# Mechanical.net
KiCad netlist of a schematic drawn in Altium Designer
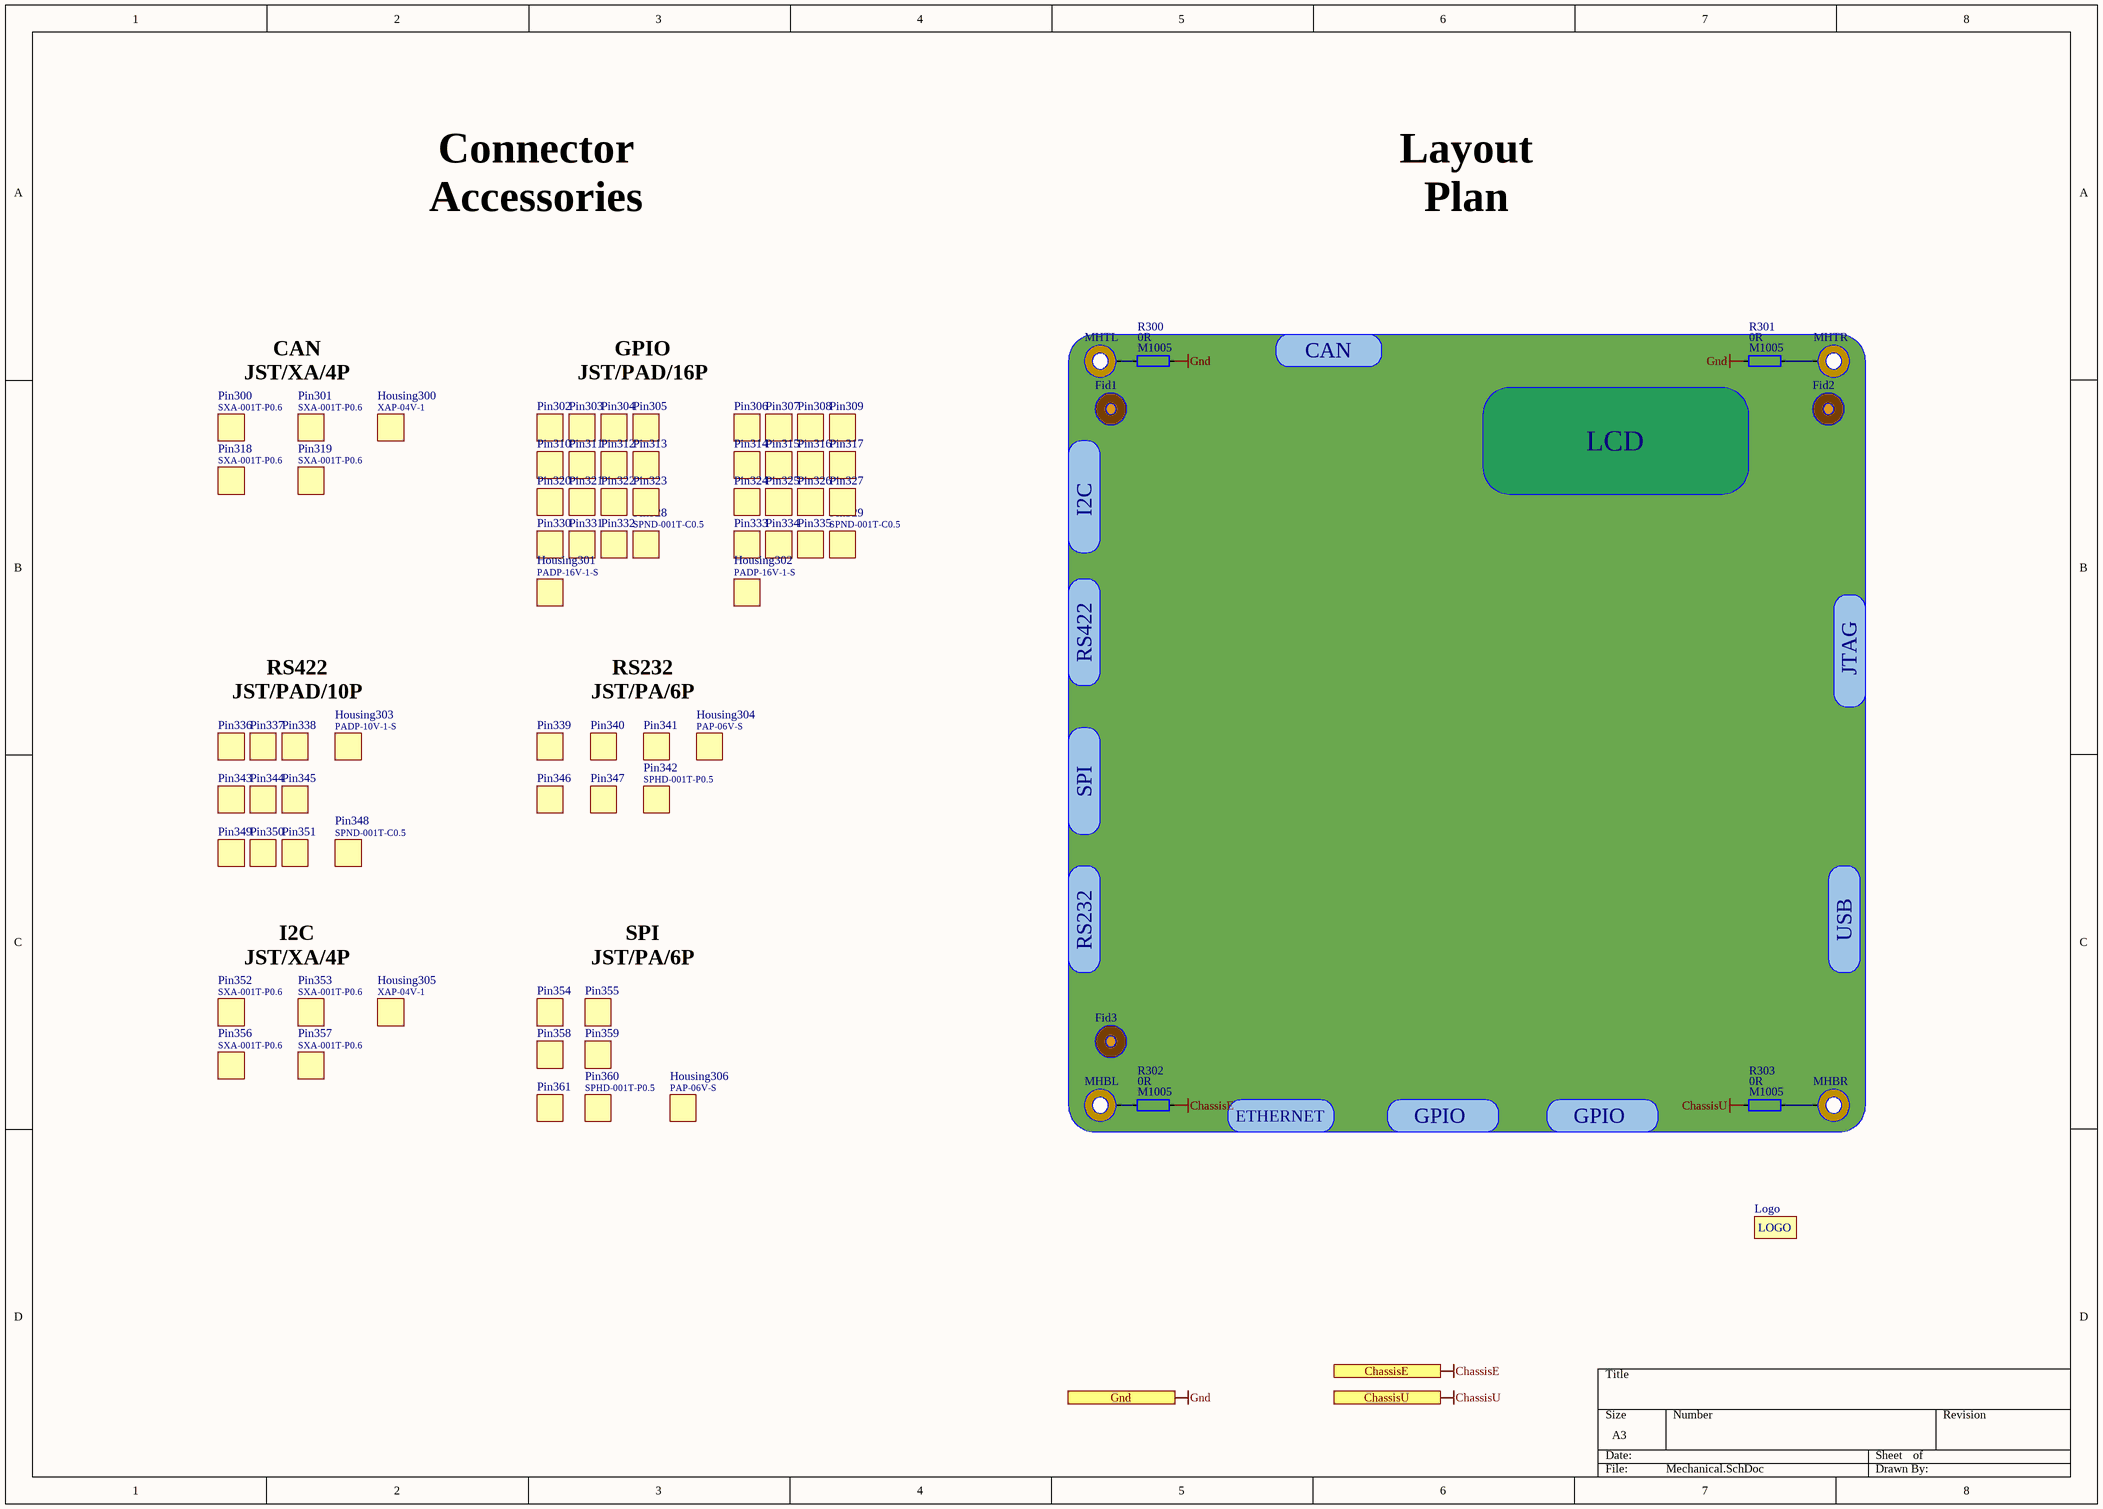
[diagram p0: Mechanical.SchDoc]

(export (version "E")
  (design (tool "Eeschema 10.0.6"))
  (components
    (comp (ref "Fid1")
      (value "Fiducial")
      (footprint "Fiducial - 2mm, 5mm")
      (description "Mechanical, Fiducial, PCB, 2mm/5mm")
      (libsource (lib "Mechanical") (part "Fiducial"))
    )
    (comp (ref "Fid2")
      (value "Fiducial")
      (footprint "Fiducial - 2mm, 5mm")
      (description "Mechanical, Fiducial, PCB, 2mm/5mm")
      (libsource (lib "Mechanical") (part "Fiducial"))
    )
    (comp (ref "Fid3")
      (value "Fiducial")
      (footprint "Fiducial - 2mm, 5mm")
      (description "Mechanical, Fiducial, PCB, 2mm/5mm")
      (libsource (lib "Mechanical") (part "Fiducial"))
    )
    (comp (ref "Housing300")
      (value "Housing")
      (footprint "Housing, PAP-06V-S")
      (description "Housing, JST, 4P, XA")
      (fields (field (name "MANUFACTURER") "JST") (field (name "MANUFACTURER PART NUMBER") "XAP-04V-1"))
      (libsource (lib "Connector - JST") (part "Housing"))
    )
    (comp (ref "Housing301")
      (value "Housing")
      (footprint "Housing, PADP-16V-1-S")
      (description "Housing, JST, 16P, PAD")
      (fields (field (name "MANUFACTURER") "JST") (field (name "MANUFACTURER PART NUMBER") "PADP-16V-1-S"))
      (libsource (lib "Connector - JST") (part "Housing"))
    )
    (comp (ref "Housing302")
      (value "Housing")
      (footprint "Housing, PADP-16V-1-S")
      (description "Housing, JST, 16P, PAD")
      (fields (field (name "MANUFACTURER") "JST") (field (name "MANUFACTURER PART NUMBER") "PADP-16V-1-S"))
      (libsource (lib "Connector - JST") (part "Housing"))
    )
    (comp (ref "Housing303")
      (value "Housing")
      (footprint "Housing, PADP-10V-1-S")
      (description "Housing, JST, 10P, PAD")
      (fields (field (name "MANUFACTURER") "JST") (field (name "MANUFACTURER PART NUMBER") "PADP-10V-1-S"))
      (libsource (lib "Connector - JST") (part "Housing"))
    )
    (comp (ref "Housing304")
      (value "Housing")
      (footprint "Housing, PAP-06V-S")
      (description "Housing, JST, PAP-06V-S")
      (fields (field (name "MANUFACTURER") "JST") (field (name "MANUFACTURER PART NUMBER") "PAP-06V-S"))
      (libsource (lib "Connector - JST") (part "Housing"))
    )
    (comp (ref "Housing305")
      (value "Housing")
      (footprint "Housing, PAP-06V-S")
      (description "Housing, JST, 4P, XA")
      (fields (field (name "MANUFACTURER") "JST") (field (name "MANUFACTURER PART NUMBER") "XAP-04V-1"))
      (libsource (lib "Connector - JST") (part "Housing"))
    )
    (comp (ref "Housing306")
      (value "Housing")
      (footprint "Housing, PAP-06V-S")
      (description "IC, Interface, FTDI, QFN-16")
      (fields (field (name "MANUFACTURER") "JST") (field (name "MANUFACTURER PART NUMBER") "PAP-06V-S"))
      (libsource (lib "Connector - JST") (part "Housing"))
    )
    (comp (ref "Logo")
      (value "Logo")
      (footprint "Logo 1")
      (description "Mechanical, Logo")
      (libsource (lib "Mechanical") (part "Logo"))
    )
    (comp (ref "MHBL")
      (value "Mounting Hole")
      (footprint "Mounting Hole - Hole-3.2mm, Pad-5mm")
      (description "Mechanical, Mounting Hole")
      (libsource (lib "Mechanical") (part "Mounting Hole"))
    )
    (comp (ref "MHBR")
      (value "Mounting Hole")
      (footprint "Mounting Hole - Hole-3.2mm, Pad-5mm")
      (description "Mechanical, Mounting Hole")
      (libsource (lib "Mechanical") (part "Mounting Hole"))
    )
    (comp (ref "MHTL")
      (value "Mounting Hole")
      (footprint "Mounting Hole - Hole-3.2mm, Pad-5mm")
      (description "Mechanical, Mounting Hole")
      (libsource (lib "Mechanical") (part "Mounting Hole"))
    )
    (comp (ref "MHTR")
      (value "Mounting Hole")
      (footprint "Mounting Hole - Hole-3.2mm, Pad-5mm")
      (description "Mechanical, Mounting Hole")
      (libsource (lib "Mechanical") (part "Mounting Hole"))
    )
    (comp (ref "Pin300")
      (value "Pin")
      (footprint "Pin, SPHD-001T-P0.5")
      (description "Pin, JST, SXA-001T-P0.6")
      (fields (field (name "MANUFACTURER") "JST") (field (name "MANUFACTURER PART NUMBER") "SXA-001T-P0.6"))
      (libsource (lib "Connector - JST") (part "Pin"))
    )
    (comp (ref "Pin301")
      (value "Pin")
      (footprint "Pin, SPHD-001T-P0.5")
      (description "Pin, JST, SXA-001T-P0.6")
      (fields (field (name "MANUFACTURER") "JST") (field (name "MANUFACTURER PART NUMBER") "SXA-001T-P0.6"))
      (libsource (lib "Connector - JST") (part "Pin"))
    )
    (comp (ref "Pin302")
      (value "Pin")
      (footprint "Pin, SPND-001T-C0.5")
      (description "Pin, JST, SPND-001T-C0.5")
      (fields (field (name "MANUFACTURER") "JST") (field (name "MANUFACTURER PART NUMBER") "SPND-001T-C0.5"))
      (libsource (lib "Connector - JST") (part "Pin"))
    )
    (comp (ref "Pin303")
      (value "Pin")
      (footprint "Pin, SPND-001T-C0.5")
      (description "Pin, JST, SPND-001T-C0.5")
      (fields (field (name "MANUFACTURER") "JST") (field (name "MANUFACTURER PART NUMBER") "SPND-001T-C0.5"))
      (libsource (lib "Connector - JST") (part "Pin"))
    )
    (comp (ref "Pin304")
      (value "Pin")
      (footprint "Pin, SPND-001T-C0.5")
      (description "Pin, JST, SPND-001T-C0.5")
      (fields (field (name "MANUFACTURER") "JST") (field (name "MANUFACTURER PART NUMBER") "SPND-001T-C0.5"))
      (libsource (lib "Connector - JST") (part "Pin"))
    )
    (comp (ref "Pin305")
      (value "Pin")
      (footprint "Pin, SPND-001T-C0.5")
      (description "Pin, JST, SPND-001T-C0.5")
      (fields (field (name "MANUFACTURER") "JST") (field (name "MANUFACTURER PART NUMBER") "SPND-001T-C0.5"))
      (libsource (lib "Connector - JST") (part "Pin"))
    )
    (comp (ref "Pin306")
      (value "Pin")
      (footprint "Pin, SPND-001T-C0.5")
      (description "Pin, JST, SPND-001T-C0.5")
      (fields (field (name "MANUFACTURER") "JST") (field (name "MANUFACTURER PART NUMBER") "SPND-001T-C0.5"))
      (libsource (lib "Connector - JST") (part "Pin"))
    )
    (comp (ref "Pin307")
      (value "Pin")
      (footprint "Pin, SPND-001T-C0.5")
      (description "Pin, JST, SPND-001T-C0.5")
      (fields (field (name "MANUFACTURER") "JST") (field (name "MANUFACTURER PART NUMBER") "SPND-001T-C0.5"))
      (libsource (lib "Connector - JST") (part "Pin"))
    )
    (comp (ref "Pin308")
      (value "Pin")
      (footprint "Pin, SPND-001T-C0.5")
      (description "Pin, JST, SPND-001T-C0.5")
      (fields (field (name "MANUFACTURER") "JST") (field (name "MANUFACTURER PART NUMBER") "SPND-001T-C0.5"))
      (libsource (lib "Connector - JST") (part "Pin"))
    )
    (comp (ref "Pin309")
      (value "Pin")
      (footprint "Pin, SPND-001T-C0.5")
      (description "Pin, JST, SPND-001T-C0.5")
      (fields (field (name "MANUFACTURER") "JST") (field (name "MANUFACTURER PART NUMBER") "SPND-001T-C0.5"))
      (libsource (lib "Connector - JST") (part "Pin"))
    )
    (comp (ref "Pin310")
      (value "Pin")
      (footprint "Pin, SPND-001T-C0.5")
      (description "Pin, JST, SPND-001T-C0.5")
      (fields (field (name "MANUFACTURER") "JST") (field (name "MANUFACTURER PART NUMBER") "SPND-001T-C0.5"))
      (libsource (lib "Connector - JST") (part "Pin"))
    )
    (comp (ref "Pin311")
      (value "Pin")
      (footprint "Pin, SPND-001T-C0.5")
      (description "Pin, JST, SPND-001T-C0.5")
      (fields (field (name "MANUFACTURER") "JST") (field (name "MANUFACTURER PART NUMBER") "SPND-001T-C0.5"))
      (libsource (lib "Connector - JST") (part "Pin"))
    )
    (comp (ref "Pin312")
      (value "Pin")
      (footprint "Pin, SPND-001T-C0.5")
      (description "Pin, JST, SPND-001T-C0.5")
      (fields (field (name "MANUFACTURER") "JST") (field (name "MANUFACTURER PART NUMBER") "SPND-001T-C0.5"))
      (libsource (lib "Connector - JST") (part "Pin"))
    )
    (comp (ref "Pin313")
      (value "Pin")
      (footprint "Pin, SPND-001T-C0.5")
      (description "Pin, JST, SPND-001T-C0.5")
      (fields (field (name "MANUFACTURER") "JST") (field (name "MANUFACTURER PART NUMBER") "SPND-001T-C0.5"))
      (libsource (lib "Connector - JST") (part "Pin"))
    )
    (comp (ref "Pin314")
      (value "Pin")
      (footprint "Pin, SPND-001T-C0.5")
      (description "Pin, JST, SPND-001T-C0.5")
      (fields (field (name "MANUFACTURER") "JST") (field (name "MANUFACTURER PART NUMBER") "SPND-001T-C0.5"))
      (libsource (lib "Connector - JST") (part "Pin"))
    )
    (comp (ref "Pin315")
      (value "Pin")
      (footprint "Pin, SPND-001T-C0.5")
      (description "Pin, JST, SPND-001T-C0.5")
      (fields (field (name "MANUFACTURER") "JST") (field (name "MANUFACTURER PART NUMBER") "SPND-001T-C0.5"))
      (libsource (lib "Connector - JST") (part "Pin"))
    )
    (comp (ref "Pin316")
      (value "Pin")
      (footprint "Pin, SPND-001T-C0.5")
      (description "Pin, JST, SPND-001T-C0.5")
      (fields (field (name "MANUFACTURER") "JST") (field (name "MANUFACTURER PART NUMBER") "SPND-001T-C0.5"))
      (libsource (lib "Connector - JST") (part "Pin"))
    )
    (comp (ref "Pin317")
      (value "Pin")
      (footprint "Pin, SPND-001T-C0.5")
      (description "Pin, JST, SPND-001T-C0.5")
      (fields (field (name "MANUFACTURER") "JST") (field (name "MANUFACTURER PART NUMBER") "SPND-001T-C0.5"))
      (libsource (lib "Connector - JST") (part "Pin"))
    )
    (comp (ref "Pin318")
      (value "Pin")
      (footprint "Pin, SPHD-001T-P0.5")
      (description "Pin, JST, SXA-001T-P0.6")
      (fields (field (name "MANUFACTURER") "JST") (field (name "MANUFACTURER PART NUMBER") "SXA-001T-P0.6"))
      (libsource (lib "Connector - JST") (part "Pin"))
    )
    (comp (ref "Pin319")
      (value "Pin")
      (footprint "Pin, SPHD-001T-P0.5")
      (description "Pin, JST, SXA-001T-P0.6")
      (fields (field (name "MANUFACTURER") "JST") (field (name "MANUFACTURER PART NUMBER") "SXA-001T-P0.6"))
      (libsource (lib "Connector - JST") (part "Pin"))
    )
    (comp (ref "Pin320")
      (value "Pin")
      (footprint "Pin, SPND-001T-C0.5")
      (description "Pin, JST, SPND-001T-C0.5")
      (fields (field (name "MANUFACTURER") "JST") (field (name "MANUFACTURER PART NUMBER") "SPND-001T-C0.5"))
      (libsource (lib "Connector - JST") (part "Pin"))
    )
    (comp (ref "Pin321")
      (value "Pin")
      (footprint "Pin, SPND-001T-C0.5")
      (description "Pin, JST, SPND-001T-C0.5")
      (fields (field (name "MANUFACTURER") "JST") (field (name "MANUFACTURER PART NUMBER") "SPND-001T-C0.5"))
      (libsource (lib "Connector - JST") (part "Pin"))
    )
    (comp (ref "Pin322")
      (value "Pin")
      (footprint "Pin, SPND-001T-C0.5")
      (description "Pin, JST, SPND-001T-C0.5")
      (fields (field (name "MANUFACTURER") "JST") (field (name "MANUFACTURER PART NUMBER") "SPND-001T-C0.5"))
      (libsource (lib "Connector - JST") (part "Pin"))
    )
    (comp (ref "Pin323")
      (value "Pin")
      (footprint "Pin, SPND-001T-C0.5")
      (description "Pin, JST, SPND-001T-C0.5")
      (fields (field (name "MANUFACTURER") "JST") (field (name "MANUFACTURER PART NUMBER") "SPND-001T-C0.5"))
      (libsource (lib "Connector - JST") (part "Pin"))
    )
    (comp (ref "Pin324")
      (value "Pin")
      (footprint "Pin, SPND-001T-C0.5")
      (description "Pin, JST, SPND-001T-C0.5")
      (fields (field (name "MANUFACTURER") "JST") (field (name "MANUFACTURER PART NUMBER") "SPND-001T-C0.5"))
      (libsource (lib "Connector - JST") (part "Pin"))
    )
    (comp (ref "Pin325")
      (value "Pin")
      (footprint "Pin, SPND-001T-C0.5")
      (description "Pin, JST, SPND-001T-C0.5")
      (fields (field (name "MANUFACTURER") "JST") (field (name "MANUFACTURER PART NUMBER") "SPND-001T-C0.5"))
      (libsource (lib "Connector - JST") (part "Pin"))
    )
    (comp (ref "Pin326")
      (value "Pin")
      (footprint "Pin, SPND-001T-C0.5")
      (description "Pin, JST, SPND-001T-C0.5")
      (fields (field (name "MANUFACTURER") "JST") (field (name "MANUFACTURER PART NUMBER") "SPND-001T-C0.5"))
      (libsource (lib "Connector - JST") (part "Pin"))
    )
    (comp (ref "Pin327")
      (value "Pin")
      (footprint "Pin, SPND-001T-C0.5")
      (description "Pin, JST, SPND-001T-C0.5")
      (fields (field (name "MANUFACTURER") "JST") (field (name "MANUFACTURER PART NUMBER") "SPND-001T-C0.5"))
      (libsource (lib "Connector - JST") (part "Pin"))
    )
    (comp (ref "Pin328")
      (value "Pin")
      (footprint "Pin, SPND-001T-C0.5")
      (description "Pin, JST, SPND-001T-C0.5")
      (fields (field (name "MANUFACTURER") "JST") (field (name "MANUFACTURER PART NUMBER") "SPND-001T-C0.5"))
      (libsource (lib "Connector - JST") (part "Pin"))
    )
    (comp (ref "Pin329")
      (value "Pin")
      (footprint "Pin, SPND-001T-C0.5")
      (description "Pin, JST, SPND-001T-C0.5")
      (fields (field (name "MANUFACTURER") "JST") (field (name "MANUFACTURER PART NUMBER") "SPND-001T-C0.5"))
      (libsource (lib "Connector - JST") (part "Pin"))
    )
    (comp (ref "Pin330")
      (value "Pin")
      (footprint "Pin, SPND-001T-C0.5")
      (description "Pin, JST, SPND-001T-C0.5")
      (fields (field (name "MANUFACTURER") "JST") (field (name "MANUFACTURER PART NUMBER") "SPND-001T-C0.5"))
      (libsource (lib "Connector - JST") (part "Pin"))
    )
    (comp (ref "Pin331")
      (value "Pin")
      (footprint "Pin, SPND-001T-C0.5")
      (description "Pin, JST, SPND-001T-C0.5")
      (fields (field (name "MANUFACTURER") "JST") (field (name "MANUFACTURER PART NUMBER") "SPND-001T-C0.5"))
      (libsource (lib "Connector - JST") (part "Pin"))
    )
    (comp (ref "Pin332")
      (value "Pin")
      (footprint "Pin, SPND-001T-C0.5")
      (description "Pin, JST, SPND-001T-C0.5")
      (fields (field (name "MANUFACTURER") "JST") (field (name "MANUFACTURER PART NUMBER") "SPND-001T-C0.5"))
      (libsource (lib "Connector - JST") (part "Pin"))
    )
    (comp (ref "Pin333")
      (value "Pin")
      (footprint "Pin, SPND-001T-C0.5")
      (description "Pin, JST, SPND-001T-C0.5")
      (fields (field (name "MANUFACTURER") "JST") (field (name "MANUFACTURER PART NUMBER") "SPND-001T-C0.5"))
      (libsource (lib "Connector - JST") (part "Pin"))
    )
    (comp (ref "Pin334")
      (value "Pin")
      (footprint "Pin, SPND-001T-C0.5")
      (description "Pin, JST, SPND-001T-C0.5")
      (fields (field (name "MANUFACTURER") "JST") (field (name "MANUFACTURER PART NUMBER") "SPND-001T-C0.5"))
      (libsource (lib "Connector - JST") (part "Pin"))
    )
    (comp (ref "Pin335")
      (value "Pin")
      (footprint "Pin, SPND-001T-C0.5")
      (description "Pin, JST, SPND-001T-C0.5")
      (fields (field (name "MANUFACTURER") "JST") (field (name "MANUFACTURER PART NUMBER") "SPND-001T-C0.5"))
      (libsource (lib "Connector - JST") (part "Pin"))
    )
    (comp (ref "Pin336")
      (value "Pin")
      (footprint "Pin, SPND-001T-C0.5")
      (description "Pin, JST, SPND-001T-C0.5")
      (fields (field (name "MANUFACTURER") "JST") (field (name "MANUFACTURER PART NUMBER") "SPND-001T-C0.5"))
      (libsource (lib "Connector - JST") (part "Pin"))
    )
    (comp (ref "Pin337")
      (value "Pin")
      (footprint "Pin, SPND-001T-C0.5")
      (description "Pin, JST, SPND-001T-C0.5")
      (fields (field (name "MANUFACTURER") "JST") (field (name "MANUFACTURER PART NUMBER") "SPND-001T-C0.5"))
      (libsource (lib "Connector - JST") (part "Pin"))
    )
    (comp (ref "Pin338")
      (value "Pin")
      (footprint "Pin, SPND-001T-C0.5")
      (description "Pin, JST, SPND-001T-C0.5")
      (fields (field (name "MANUFACTURER") "JST") (field (name "MANUFACTURER PART NUMBER") "SPND-001T-C0.5"))
      (libsource (lib "Connector - JST") (part "Pin"))
    )
    (comp (ref "Pin339")
      (value "Pin")
      (footprint "Pin, SPHD-001T-P0.5")
      (description "Pin, JST, SPHD-001T-P0.5")
      (fields (field (name "MANUFACTURER") "JST") (field (name "MANUFACTURER PART NUMBER") "SPHD-001T-P0.5"))
      (libsource (lib "Connector - JST") (part "Pin"))
    )
    (comp (ref "Pin340")
      (value "Pin")
      (footprint "Pin, SPHD-001T-P0.5")
      (description "Pin, JST, SPHD-001T-P0.5")
      (fields (field (name "MANUFACTURER") "JST") (field (name "MANUFACTURER PART NUMBER") "SPHD-001T-P0.5"))
      (libsource (lib "Connector - JST") (part "Pin"))
    )
    (comp (ref "Pin341")
      (value "Pin")
      (footprint "Pin, SPHD-001T-P0.5")
      (description "Pin, JST, SPHD-001T-P0.5")
      (fields (field (name "MANUFACTURER") "JST") (field (name "MANUFACTURER PART NUMBER") "SPHD-001T-P0.5"))
      (libsource (lib "Connector - JST") (part "Pin"))
    )
    (comp (ref "Pin342")
      (value "Pin")
      (footprint "Pin, SPHD-001T-P0.5")
      (description "Pin, JST, SPHD-001T-P0.5")
      (fields (field (name "MANUFACTURER") "JST") (field (name "MANUFACTURER PART NUMBER") "SPHD-001T-P0.5"))
      (libsource (lib "Connector - JST") (part "Pin"))
    )
    (comp (ref "Pin343")
      (value "Pin")
      (footprint "Pin, SPND-001T-C0.5")
      (description "Pin, JST, SPND-001T-C0.5")
      (fields (field (name "MANUFACTURER") "JST") (field (name "MANUFACTURER PART NUMBER") "SPND-001T-C0.5"))
      (libsource (lib "Connector - JST") (part "Pin"))
    )
    (comp (ref "Pin344")
      (value "Pin")
      (footprint "Pin, SPND-001T-C0.5")
      (description "Pin, JST, SPND-001T-C0.5")
      (fields (field (name "MANUFACTURER") "JST") (field (name "MANUFACTURER PART NUMBER") "SPND-001T-C0.5"))
      (libsource (lib "Connector - JST") (part "Pin"))
    )
    (comp (ref "Pin345")
      (value "Pin")
      (footprint "Pin, SPND-001T-C0.5")
      (description "Pin, JST, SPND-001T-C0.5")
      (fields (field (name "MANUFACTURER") "JST") (field (name "MANUFACTURER PART NUMBER") "SPND-001T-C0.5"))
      (libsource (lib "Connector - JST") (part "Pin"))
    )
    (comp (ref "Pin346")
      (value "Pin")
      (footprint "Pin, SPHD-001T-P0.5")
      (description "Pin, JST, SPHD-001T-P0.5")
      (fields (field (name "MANUFACTURER") "JST") (field (name "MANUFACTURER PART NUMBER") "SPHD-001T-P0.5"))
      (libsource (lib "Connector - JST") (part "Pin"))
    )
    (comp (ref "Pin347")
      (value "Pin")
      (footprint "Pin, SPHD-001T-P0.5")
      (description "Pin, JST, SPHD-001T-P0.5")
      (fields (field (name "MANUFACTURER") "JST") (field (name "MANUFACTURER PART NUMBER") "SPHD-001T-P0.5"))
      (libsource (lib "Connector - JST") (part "Pin"))
    )
    (comp (ref "Pin348")
      (value "Pin")
      (footprint "Pin, SPND-001T-C0.5")
      (description "Pin, JST, SPND-001T-C0.5")
      (fields (field (name "MANUFACTURER") "JST") (field (name "MANUFACTURER PART NUMBER") "SPND-001T-C0.5"))
      (libsource (lib "Connector - JST") (part "Pin"))
    )
    (comp (ref "Pin349")
      (value "Pin")
      (footprint "Pin, SPND-001T-C0.5")
      (description "Pin, JST, SPND-001T-C0.5")
      (fields (field (name "MANUFACTURER") "JST") (field (name "MANUFACTURER PART NUMBER") "SPND-001T-C0.5"))
      (libsource (lib "Connector - JST") (part "Pin"))
    )
    (comp (ref "Pin350")
      (value "Pin")
      (footprint "Pin, SPND-001T-C0.5")
      (description "Pin, JST, SPND-001T-C0.5")
      (fields (field (name "MANUFACTURER") "JST") (field (name "MANUFACTURER PART NUMBER") "SPND-001T-C0.5"))
      (libsource (lib "Connector - JST") (part "Pin"))
    )
    (comp (ref "Pin351")
      (value "Pin")
      (footprint "Pin, SPND-001T-C0.5")
      (description "Pin, JST, SPND-001T-C0.5")
      (fields (field (name "MANUFACTURER") "JST") (field (name "MANUFACTURER PART NUMBER") "SPND-001T-C0.5"))
      (libsource (lib "Connector - JST") (part "Pin"))
    )
    (comp (ref "Pin352")
      (value "Pin")
      (footprint "Pin, SPHD-001T-P0.5")
      (description "Pin, JST, SXA-001T-P0.6")
      (fields (field (name "MANUFACTURER") "JST") (field (name "MANUFACTURER PART NUMBER") "SXA-001T-P0.6"))
      (libsource (lib "Connector - JST") (part "Pin"))
    )
    (comp (ref "Pin353")
      (value "Pin")
      (footprint "Pin, SPHD-001T-P0.5")
      (description "Pin, JST, SXA-001T-P0.6")
      (fields (field (name "MANUFACTURER") "JST") (field (name "MANUFACTURER PART NUMBER") "SXA-001T-P0.6"))
      (libsource (lib "Connector - JST") (part "Pin"))
    )
    (comp (ref "Pin354")
      (value "Pin")
      (footprint "Pin, SPHD-001T-P0.5")
      (description "IC, Interface, FTDI, QFN-16")
      (fields (field (name "MANUFACTURER") "JST") (field (name "MANUFACTURER PART NUMBER") "SPHD-001T-P0.5"))
      (libsource (lib "Connector - JST") (part "Pin"))
    )
    (comp (ref "Pin355")
      (value "Pin")
      (footprint "Pin, SPHD-001T-P0.5")
      (description "IC, Interface, FTDI, QFN-16")
      (fields (field (name "MANUFACTURER") "JST") (field (name "MANUFACTURER PART NUMBER") "SPHD-001T-P0.5"))
      (libsource (lib "Connector - JST") (part "Pin"))
    )
    (comp (ref "Pin356")
      (value "Pin")
      (footprint "Pin, SPHD-001T-P0.5")
      (description "Pin, JST, SXA-001T-P0.6")
      (fields (field (name "MANUFACTURER") "JST") (field (name "MANUFACTURER PART NUMBER") "SXA-001T-P0.6"))
      (libsource (lib "Connector - JST") (part "Pin"))
    )
    (comp (ref "Pin357")
      (value "Pin")
      (footprint "Pin, SPHD-001T-P0.5")
      (description "Pin, JST, SXA-001T-P0.6")
      (fields (field (name "MANUFACTURER") "JST") (field (name "MANUFACTURER PART NUMBER") "SXA-001T-P0.6"))
      (libsource (lib "Connector - JST") (part "Pin"))
    )
    (comp (ref "Pin358")
      (value "Pin")
      (footprint "Pin, SPHD-001T-P0.5")
      (description "IC, Interface, FTDI, QFN-16")
      (fields (field (name "MANUFACTURER") "JST") (field (name "MANUFACTURER PART NUMBER") "SPHD-001T-P0.5"))
      (libsource (lib "Connector - JST") (part "Pin"))
    )
    (comp (ref "Pin359")
      (value "Pin")
      (footprint "Pin, SPHD-001T-P0.5")
      (description "IC, Interface, FTDI, QFN-16")
      (fields (field (name "MANUFACTURER") "JST") (field (name "MANUFACTURER PART NUMBER") "SPHD-001T-P0.5"))
      (libsource (lib "Connector - JST") (part "Pin"))
    )
    (comp (ref "Pin360")
      (value "Pin")
      (footprint "Pin, SPHD-001T-P0.5")
      (description "IC, Interface, FTDI, QFN-16")
      (fields (field (name "MANUFACTURER") "JST") (field (name "MANUFACTURER PART NUMBER") "SPHD-001T-P0.5"))
      (libsource (lib "Connector - JST") (part "Pin"))
    )
    (comp (ref "Pin361")
      (value "Pin")
      (footprint "Pin, SPHD-001T-P0.5")
      (description "IC, Interface, FTDI, QFN-16")
      (fields (field (name "MANUFACTURER") "JST") (field (name "MANUFACTURER PART NUMBER") "SPHD-001T-P0.5"))
      (libsource (lib "Connector - JST") (part "Pin"))
    )
    (comp (ref "R300")
      (value "0R")
      (footprint "Resistor_Smd_M1005_I0402")
      (description "Res, 0R, M1005")
      (fields
        (field (name "MANUFACTURER") "Yageo")
        (field (name "MANUFACTURER PART NUMBER") "RC0402FR-070RL")
        (field (name "PACKAGE") "M1005")
      )
      (libsource (lib "Resistor") (part "Resistor"))
    )
    (comp (ref "R301")
      (value "0R")
      (footprint "Resistor_Smd_M1005_I0402")
      (description "Res, 0R, M1005")
      (fields
        (field (name "MANUFACTURER") "Yageo")
        (field (name "MANUFACTURER PART NUMBER") "RC0402FR-070RL")
        (field (name "PACKAGE") "M1005")
      )
      (libsource (lib "Resistor") (part "Resistor"))
    )
    (comp (ref "R302")
      (value "0R")
      (footprint "Resistor_Smd_M1005_I0402")
      (description "Res, 0R, M1005")
      (fields
        (field (name "MANUFACTURER") "Yageo")
        (field (name "MANUFACTURER PART NUMBER") "RC0402FR-070RL")
        (field (name "PACKAGE") "M1005")
      )
      (libsource (lib "Resistor") (part "Resistor"))
    )
    (comp (ref "R303")
      (value "0R")
      (footprint "Resistor_Smd_M1005_I0402")
      (description "Res, 0R, M1005")
      (fields
        (field (name "MANUFACTURER") "Yageo")
        (field (name "MANUFACTURER PART NUMBER") "RC0402FR-070RL")
        (field (name "PACKAGE") "M1005")
      )
      (libsource (lib "Resistor") (part "Resistor"))
    )
  )
  (nets
    (net (code "1") (name "ChassisE") (class "Default")
      (node (ref "R302") (pin "2") (pinfunction "2_2") (pintype "passive"))
    )
    (net (code "2") (name "ChassisU") (class "Default")
      (node (ref "R303") (pin "1") (pinfunction "1_1") (pintype "passive"))
    )
    (net (code "3") (name "Gnd") (class "Default")
      (node (ref "R300") (pin "2") (pinfunction "2_2") (pintype "passive"))
      (node (ref "R301") (pin "1") (pinfunction "1_1") (pintype "passive"))
    )
    (net (code "4") (name "Net-(MHBL-PadHole)") (class "Default")
      (node (ref "MHBL") (pin "Hole") (pinfunction "Hole_Hole") (pintype "passive"))
      (node (ref "R302") (pin "1") (pinfunction "1_1") (pintype "passive"))
    )
    (net (code "5") (name "Net-(MHBR-PadHole)") (class "Default")
      (node (ref "MHBR") (pin "Hole") (pinfunction "Hole_Hole") (pintype "passive"))
      (node (ref "R303") (pin "2") (pinfunction "2_2") (pintype "passive"))
    )
    (net (code "6") (name "Net-(MHTL-PadHole)") (class "Default")
      (node (ref "MHTL") (pin "Hole") (pinfunction "Hole_Hole") (pintype "passive"))
      (node (ref "R300") (pin "1") (pinfunction "1_1") (pintype "passive"))
    )
    (net (code "7") (name "Net-(MHTR-PadHole)") (class "Default")
      (node (ref "MHTR") (pin "Hole") (pinfunction "Hole_Hole") (pintype "passive"))
      (node (ref "R301") (pin "2") (pinfunction "2_2") (pintype "passive"))
    )
  )
)
